# 5_rf_path.net
KiCad netlist of a schematic drawn in Altium Designer
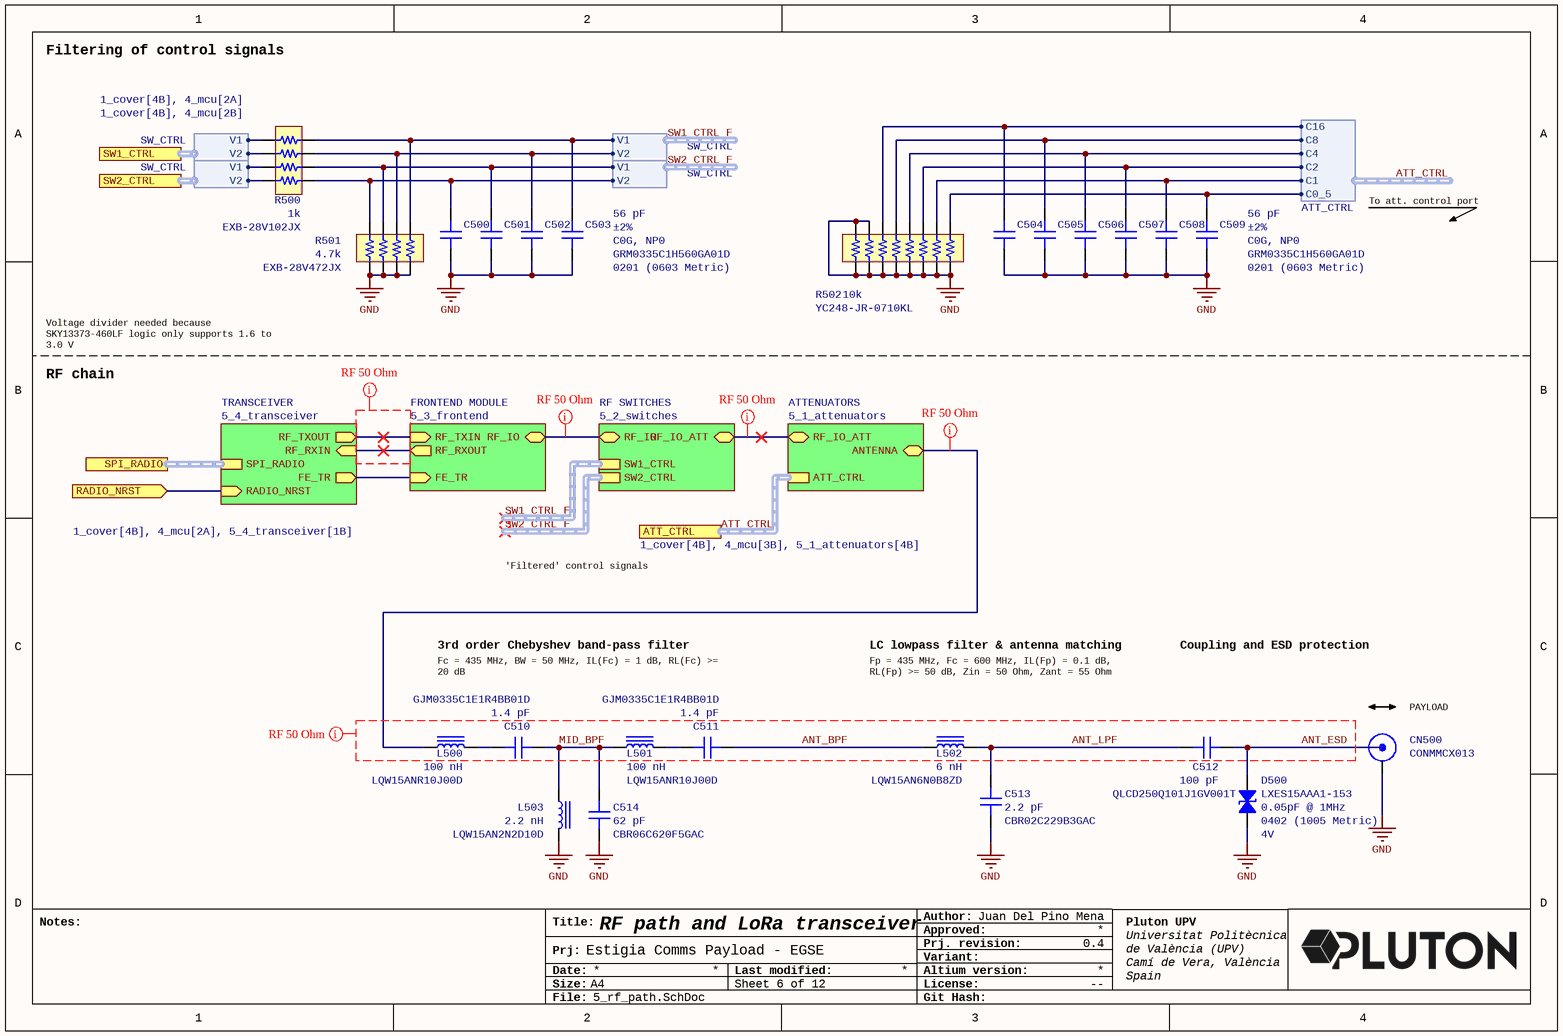
[diagram p0: 5_rf_path.SchDoc]

(export (version "E")
  (design (tool "Eeschema 10.0.6"))
  (components
    (comp (ref "C500")
      (value "56 pF")
      (footprint "CAP 0201_0603")
      (description "CAP CER 56PF 50V C0G/NP0 0201")
      (fields
        (field (name "PART NUMBER") "GRM0335C1H560GA01D")
        (field (name "MANUFACTURER") "Murata Electronics")
      )
      (libsource (lib "Celestial Altium Library - altium_library") (part "Capacitor"))
    )
    (comp (ref "C501")
      (value "56 pF")
      (footprint "CAP 0201_0603")
      (description "CAP CER 56PF 50V C0G/NP0 0201")
      (fields
        (field (name "PART NUMBER") "GRM0335C1H560GA01D")
        (field (name "MANUFACTURER") "Murata Electronics")
      )
      (libsource (lib "Celestial Altium Library - altium_library") (part "Capacitor"))
    )
    (comp (ref "C502")
      (value "56 pF")
      (footprint "CAP 0201_0603")
      (description "CAP CER 56PF 50V C0G/NP0 0201")
      (fields
        (field (name "PART NUMBER") "GRM0335C1H560GA01D")
        (field (name "MANUFACTURER") "Murata Electronics")
      )
      (libsource (lib "Celestial Altium Library - altium_library") (part "Capacitor"))
    )
    (comp (ref "C503")
      (value "56 pF")
      (footprint "CAP 0201_0603")
      (description "CAP CER 56PF 50V C0G/NP0 0201")
      (fields
        (field (name "PART NUMBER") "GRM0335C1H560GA01D")
        (field (name "MANUFACTURER") "Murata Electronics")
        (field (name "PACKAGE / CASE") "0201 (0603 Metric)")
        (field (name "TEMPERATURE COEFFICIENT") "C0G, NP0")
        (field (name "TOLERANCE") "±2%")
      )
      (libsource (lib "Celestial Altium Library - altium_library") (part "Capacitor"))
    )
    (comp (ref "C504")
      (value "56 pF")
      (footprint "CAP 0201_0603")
      (description "CAP CER 56PF 50V C0G/NP0 0201")
      (fields
        (field (name "PART NUMBER") "GRM0335C1H560GA01D")
        (field (name "MANUFACTURER") "Murata Electronics")
      )
      (libsource (lib "Celestial Altium Library - altium_library") (part "Capacitor"))
    )
    (comp (ref "C505")
      (value "56 pF")
      (footprint "CAP 0201_0603")
      (description "CAP CER 56PF 50V C0G/NP0 0201")
      (fields
        (field (name "PART NUMBER") "GRM0335C1H560GA01D")
        (field (name "MANUFACTURER") "Murata Electronics")
      )
      (libsource (lib "Celestial Altium Library - altium_library") (part "Capacitor"))
    )
    (comp (ref "C506")
      (value "56 pF")
      (footprint "CAP 0201_0603")
      (description "CAP CER 56PF 50V C0G/NP0 0201")
      (fields
        (field (name "PART NUMBER") "GRM0335C1H560GA01D")
        (field (name "MANUFACTURER") "Murata Electronics")
      )
      (libsource (lib "Celestial Altium Library - altium_library") (part "Capacitor"))
    )
    (comp (ref "C507")
      (value "56 pF")
      (footprint "CAP 0201_0603")
      (description "CAP CER 56PF 50V C0G/NP0 0201")
      (fields
        (field (name "PART NUMBER") "GRM0335C1H560GA01D")
        (field (name "MANUFACTURER") "Murata Electronics")
      )
      (libsource (lib "Celestial Altium Library - altium_library") (part "Capacitor"))
    )
    (comp (ref "C508")
      (value "56 pF")
      (footprint "CAP 0201_0603")
      (description "CAP CER 56PF 50V C0G/NP0 0201")
      (fields
        (field (name "PART NUMBER") "GRM0335C1H560GA01D")
        (field (name "MANUFACTURER") "Murata Electronics")
      )
      (libsource (lib "Celestial Altium Library - altium_library") (part "Capacitor"))
    )
    (comp (ref "C509")
      (value "56 pF")
      (footprint "CAP 0201_0603")
      (description "CAP CER 56PF 50V C0G/NP0 0201")
      (fields
        (field (name "PART NUMBER") "GRM0335C1H560GA01D")
        (field (name "MANUFACTURER") "Murata Electronics")
        (field (name "PACKAGE / CASE") "0201 (0603 Metric)")
        (field (name "TEMPERATURE COEFFICIENT") "C0G, NP0")
        (field (name "TOLERANCE") "±2%")
      )
      (libsource (lib "Celestial Altium Library - altium_library") (part "Capacitor"))
    )
    (comp (ref "C510")
      (value "1.4 pF")
      (footprint "CAP 0201_0603 RF")
      (description "CAP CER 1.4PF 25V C0G/NP0 0201")
      (fields
        (field (name "PART NUMBER") "GJM0335C1E1R4BB01D")
        (field (name "MANUFACTURER") "Murata Electronics")
        (field (name "TOLERANCE") "±0.1pF")
      )
      (libsource (lib "Celestial Altium Library - altium_library") (part "Capacitor"))
    )
    (comp (ref "C511")
      (value "1.4 pF")
      (footprint "CAP 0201_0603 RF")
      (description "CAP CER 1.4PF 25V C0G/NP0 0201")
      (fields
        (field (name "PART NUMBER") "GJM0335C1E1R4BB01D")
        (field (name "MANUFACTURER") "Murata Electronics")
        (field (name "TOLERANCE") "±0.1pF")
      )
      (libsource (lib "Celestial Altium Library - altium_library") (part "Capacitor"))
    )
    (comp (ref "C512")
      (value "100 pF")
      (footprint "CAP 0201_0603 RF")
      (description "CAP CER 100PF 25V C0G/NP0 0201")
      (fields
        (field (name "PART NUMBER") "QLCD250Q101J1GV001T")
        (field (name "CAPACITANCE") "100 pF")
        (field (name "MANUFACTURER") "Johanson Technology Inc.")
        (field (name "TOLERANCE") "±5%")
      )
      (libsource (lib "Celestial Altium Library - altium_library") (part "Capacitor"))
    )
    (comp (ref "C513")
      (value "2.2 pF")
      (footprint "CAP 0201_0603 RF")
      (description "CAP CER 2.2PF 25V C0G/NP0 0201")
      (fields
        (field (name "PART NUMBER") "CBR02C229B3GAC")
        (field (name "MANUFACTURER") "KEMET")
        (field (name "TOLERANCE") "±0.1pF")
      )
      (libsource (lib "Celestial Altium Library - altium_library") (part "Capacitor"))
    )
    (comp (ref "C514")
      (value "62 pF")
      (footprint "CAP 0603_1608 RF")
      (description "CAP CER 62PF 50V C0G/NP0 0603")
      (fields
        (field (name "PART NUMBER") "CBR06C620F5GAC")
        (field (name "CAPACITANCE") "62 pF")
        (field (name "MANUFACTURER") "KEMET")
        (field (name "TOLERANCE") "±1%")
      )
      (libsource (lib "Celestial Altium Library - altium_library") (part "Capacitor"))
    )
    (comp (ref "CN500")
      (value "CONMMCX013")
      (footprint "connectors:CONMMCX013")
      (description "MMCX Jack PCB Cutout Edge Mount Connector 0 to 8.5 GHz operation MMCX (female socket) connection")
      (libsource (lib "connectors") (part "MMCX-CONMMCX013"))
    )
    (comp (ref "D500")
      (value "LXES15AAA1-153")
      (footprint "0402")
      (description "TVS DIODE 4V 1005")
      (fields
        (field (name "PART NUMBER") "LXES15AAA1-153")
        (field (name "CAPACITANCE @ FREQUENCY") "0.05pF @ 1MHz")
        (field (name "DEVICE PACKAGE") "0402 (1005 Metric)")
        (field (name "MANUFACTURER") "Murata Electronics")
        (field (name "VOLTAGE - REVERSE STANDOFF (TYP)") "4V")
      )
      (libsource (lib "Celestial Altium Library - altium_library") (part "Diode TVS"))
    )
    (comp (ref "L500")
      (value "100 nH")
      (footprint "IND 0402_1005 RF WW")
      (description "FIXED IND 100NH 120MA 2.52OHM SM")
      (fields
        (field (name "PART NUMBER") "LQW15ANR10J00D")
        (field (name "MANUFACTURER") "Murata Electronics")
        (field (name "TOLERANCE") "±5%")
      )
      (libsource (lib "Celestial Altium Library - altium_library") (part "Inductor"))
    )
    (comp (ref "L501")
      (value "100 nH")
      (footprint "IND 0402_1005 RF WW")
      (description "FIXED IND 100NH 120MA 2.52OHM SM")
      (fields
        (field (name "PART NUMBER") "LQW15ANR10J00D")
        (field (name "MANUFACTURER") "Murata Electronics")
        (field (name "TOLERANCE") "±5%")
      )
      (libsource (lib "Celestial Altium Library - altium_library") (part "Inductor"))
    )
    (comp (ref "L502")
      (value "6 nH")
      (footprint "IND 0402_1005 RF WW")
      (description "FIXED IND 6NH 1.6A 0.056OHM SMD")
      (fields
        (field (name "PART NUMBER") "LQW15AN6N0B8ZD")
        (field (name "MANUFACTURER") "Murata Electronics")
        (field (name "TOLERANCE") "±0.1nH")
      )
      (libsource (lib "Celestial Altium Library - altium_library") (part "Inductor"))
    )
    (comp (ref "L503")
      (value "2.2 nH")
      (footprint "IND 0402_1005 RF WW")
      (description "FIXED IND 2.2NH 1A 0.027OHM SMD")
      (fields
        (field (name "PART NUMBER") "LQW15AN2N2D10D")
        (field (name "MANUFACTURER") "Murata Electronics")
        (field (name "TOLERANCE") "±0.5nH")
      )
      (libsource (lib "Celestial Altium Library - altium_library") (part "Inductor"))
    )
    (comp (ref "R500")
      (value "EXB-28V102JX")
      (footprint "RESNET 0804-8 CONVEX")
      (description "RES ARRAY 4 RES 1K OHM 0804")
      (fields
        (field (name "PART NUMBER") "EXB-28V102JX")
        (field (name "MANUFACTURER") "Panasonic Electronic Components")
        (field (name "RESISTANCE (OHMS)") "1k")
        (field (name "TOLERANCE") "±5%")
      )
      (libsource (lib "Celestial Altium Library - altium_library") (part "Resistor Array (4 circuit)"))
    )
    (comp (ref "R501")
      (value "EXB-28V472JX")
      (footprint "RESNET 0804-8 CONVEX")
      (description "RES ARRAY 4 RES 4.7K OHM 0804")
      (fields
        (field (name "PART NUMBER") "EXB-28V472JX")
        (field (name "MANUFACTURER") "Panasonic Electronic Components")
        (field (name "RESISTANCE (OHMS)") "4.7k")
        (field (name "TOLERANCE") "±5%")
      )
      (libsource (lib "") (part "Resistor Array (4 circuit)_1"))
    )
    (comp (ref "R502")
      (value "YC248-JR-0710KL")
      (footprint "RESNET 1606-16 CONVEX")
      (description "RES ARRAY 8 RES 10K OHM 1606")
      (fields
        (field (name "PART NUMBER") "YC248-JR-0710KL")
        (field (name "MANUFACTURER") "Yageo")
        (field (name "RESISTANCE (OHMS)") "10k")
        (field (name "TOLERANCE") "±5%")
      )
      (libsource (lib "Celestial Altium Library - altium_library") (part "Resistor Array (8 Circuit)"))
    )
  )
  (nets
    (net (code "7") (name "/ANTENNA") (class "Default")
      (node (ref "L500") (pin "1") (pinfunction "1_1") (pintype "passive"))
    )
    (net (code "8") (name "/ANT_BPF") (class "Default")
      (node (ref "C511") (pin "2") (pinfunction "2_2") (pintype "passive"))
      (node (ref "L502") (pin "1") (pinfunction "1_1") (pintype "passive"))
    )
    (net (code "9") (name "/ANT_ESD") (class "Default")
      (node (ref "C512") (pin "2") (pinfunction "2_2") (pintype "passive"))
      (node (ref "CN500") (pin "1") (pinfunction "SIGNAL_1") (pintype "passive"))
      (node (ref "D500") (pin "2") (pinfunction "2_2") (pintype "passive"))
    )
    (net (code "10") (name "/ANT_LPF") (class "Default")
      (node (ref "C512") (pin "1") (pinfunction "1_1") (pintype "passive"))
      (node (ref "C513") (pin "2") (pinfunction "2_2") (pintype "passive"))
      (node (ref "L502") (pin "2") (pinfunction "2_2") (pintype "passive"))
    )
    (net (code "12") (name "/C0_5") (class "Default")
      (node (ref "C509") (pin "2") (pinfunction "2_2") (pintype "passive"))
      (node (ref "R502") (pin "9") (pinfunction "9_9") (pintype "passive"))
    )
    (net (code "13") (name "/C1") (class "Default")
      (node (ref "C508") (pin "2") (pinfunction "2_2") (pintype "passive"))
      (node (ref "R502") (pin "10") (pinfunction "10_10") (pintype "passive"))
    )
    (net (code "14") (name "/C2") (class "Default")
      (node (ref "C507") (pin "2") (pinfunction "2_2") (pintype "passive"))
      (node (ref "R502") (pin "11") (pinfunction "11_11") (pintype "passive"))
    )
    (net (code "15") (name "/C4") (class "Default")
      (node (ref "C506") (pin "2") (pinfunction "2_2") (pintype "passive"))
      (node (ref "R502") (pin "12") (pinfunction "12_12") (pintype "passive"))
    )
    (net (code "16") (name "/C8") (class "Default")
      (node (ref "C505") (pin "2") (pinfunction "2_2") (pintype "passive"))
      (node (ref "R502") (pin "13") (pinfunction "13_13") (pintype "passive"))
    )
    (net (code "17") (name "/C16") (class "Default")
      (node (ref "C504") (pin "2") (pinfunction "2_2") (pintype "passive"))
      (node (ref "R502") (pin "14") (pinfunction "14_14") (pintype "passive"))
    )
    (net (code "19") (name "/MID_BPF") (class "Default")
      (node (ref "C510") (pin "2") (pinfunction "2_2") (pintype "passive"))
      (node (ref "C514") (pin "2") (pinfunction "2_2") (pintype "passive"))
      (node (ref "L501") (pin "1") (pinfunction "1_1") (pintype "passive"))
      (node (ref "L503") (pin "1") (pinfunction "1_1") (pintype "passive"))
    )
    (net (code "29") (name "GND") (class "Default")
      (node (ref "C500") (pin "1") (pinfunction "1_1") (pintype "passive"))
      (node (ref "C501") (pin "1") (pinfunction "1_1") (pintype "passive"))
      (node (ref "C502") (pin "1") (pinfunction "1_1") (pintype "passive"))
      (node (ref "C503") (pin "1") (pinfunction "1_1") (pintype "passive"))
      (node (ref "C504") (pin "1") (pinfunction "1_1") (pintype "passive"))
      (node (ref "C505") (pin "1") (pinfunction "1_1") (pintype "passive"))
      (node (ref "C506") (pin "1") (pinfunction "1_1") (pintype "passive"))
      (node (ref "C507") (pin "1") (pinfunction "1_1") (pintype "passive"))
      (node (ref "C508") (pin "1") (pinfunction "1_1") (pintype "passive"))
      (node (ref "C509") (pin "1") (pinfunction "1_1") (pintype "passive"))
      (node (ref "C513") (pin "1") (pinfunction "1_1") (pintype "passive"))
      (node (ref "C514") (pin "1") (pinfunction "1_1") (pintype "passive"))
      (node (ref "CN500") (pin "2") (pinfunction "GND_2") (pintype "passive"))
      (node (ref "D500") (pin "1") (pinfunction "1_1") (pintype "passive"))
      (node (ref "L503") (pin "2") (pinfunction "2_2") (pintype "passive"))
      (node (ref "R501") (pin "5") (pinfunction "5_5") (pintype "passive"))
      (node (ref "R501") (pin "6") (pinfunction "6_6") (pintype "passive"))
      (node (ref "R501") (pin "7") (pinfunction "7_7") (pintype "passive"))
      (node (ref "R501") (pin "8") (pinfunction "8_8") (pintype "passive"))
      (node (ref "R502") (pin "1") (pinfunction "1_1") (pintype "passive"))
      (node (ref "R502") (pin "15") (pinfunction "15_15") (pintype "passive"))
      (node (ref "R502") (pin "16") (pinfunction "16_16") (pintype "passive"))
      (node (ref "R502") (pin "2") (pinfunction "2_2") (pintype "passive"))
      (node (ref "R502") (pin "3") (pinfunction "3_3") (pintype "passive"))
      (node (ref "R502") (pin "4") (pinfunction "4_4") (pintype "passive"))
      (node (ref "R502") (pin "5") (pinfunction "6_5") (pintype "passive"))
      (node (ref "R502") (pin "6") (pinfunction "6_6") (pintype "passive"))
      (node (ref "R502") (pin "7") (pinfunction "7_7") (pintype "passive"))
      (node (ref "R502") (pin "8") (pinfunction "8_8") (pintype "passive"))
    )
    (net (code "30") (name "Net-(C500-Pad2)") (class "Default")
      (node (ref "C500") (pin "2") (pinfunction "2_2") (pintype "passive"))
      (node (ref "R500") (pin "5") (pinfunction "5_5") (pintype "passive"))
      (node (ref "R501") (pin "4") (pinfunction "4_4") (pintype "passive"))
    )
    (net (code "31") (name "Net-(C501-Pad2)") (class "Default")
      (node (ref "C501") (pin "2") (pinfunction "2_2") (pintype "passive"))
      (node (ref "R500") (pin "6") (pinfunction "6_6") (pintype "passive"))
      (node (ref "R501") (pin "3") (pinfunction "3_3") (pintype "passive"))
    )
    (net (code "32") (name "Net-(C502-Pad2)") (class "Default")
      (node (ref "C502") (pin "2") (pinfunction "2_2") (pintype "passive"))
      (node (ref "R500") (pin "7") (pinfunction "7_7") (pintype "passive"))
      (node (ref "R501") (pin "2") (pinfunction "2_2") (pintype "passive"))
    )
    (net (code "33") (name "Net-(C503-Pad2)") (class "Default")
      (node (ref "C503") (pin "2") (pinfunction "2_2") (pintype "passive"))
      (node (ref "R500") (pin "8") (pinfunction "8_8") (pintype "passive"))
      (node (ref "R501") (pin "1") (pinfunction "1_1") (pintype "passive"))
    )
    (net (code "34") (name "Net-(C510-Pad1)") (class "Default")
      (node (ref "C510") (pin "1") (pinfunction "1_1") (pintype "passive"))
      (node (ref "L500") (pin "2") (pinfunction "2_2") (pintype "passive"))
    )
    (net (code "35") (name "Net-(C511-Pad1)") (class "Default")
      (node (ref "C511") (pin "1") (pinfunction "1_1") (pintype "passive"))
      (node (ref "L501") (pin "2") (pinfunction "2_2") (pintype "passive"))
    )
    (net (code "36") (name "unconnected-(R500-Pad1)") (class "Default")
      (node (ref "R500") (pin "1") (pinfunction "1_1") (pintype "passive"))
    )
    (net (code "37") (name "unconnected-(R500-Pad2)") (class "Default")
      (node (ref "R500") (pin "2") (pinfunction "2_2") (pintype "passive"))
    )
    (net (code "38") (name "unconnected-(R500-Pad3)") (class "Default")
      (node (ref "R500") (pin "3") (pinfunction "3_3") (pintype "passive"))
    )
    (net (code "39") (name "unconnected-(R500-Pad4)") (class "Default")
      (node (ref "R500") (pin "4") (pinfunction "4_4") (pintype "passive"))
    )
  )
)
